# MK1.net
KiCad netlist of a schematic drawn in EAGLE
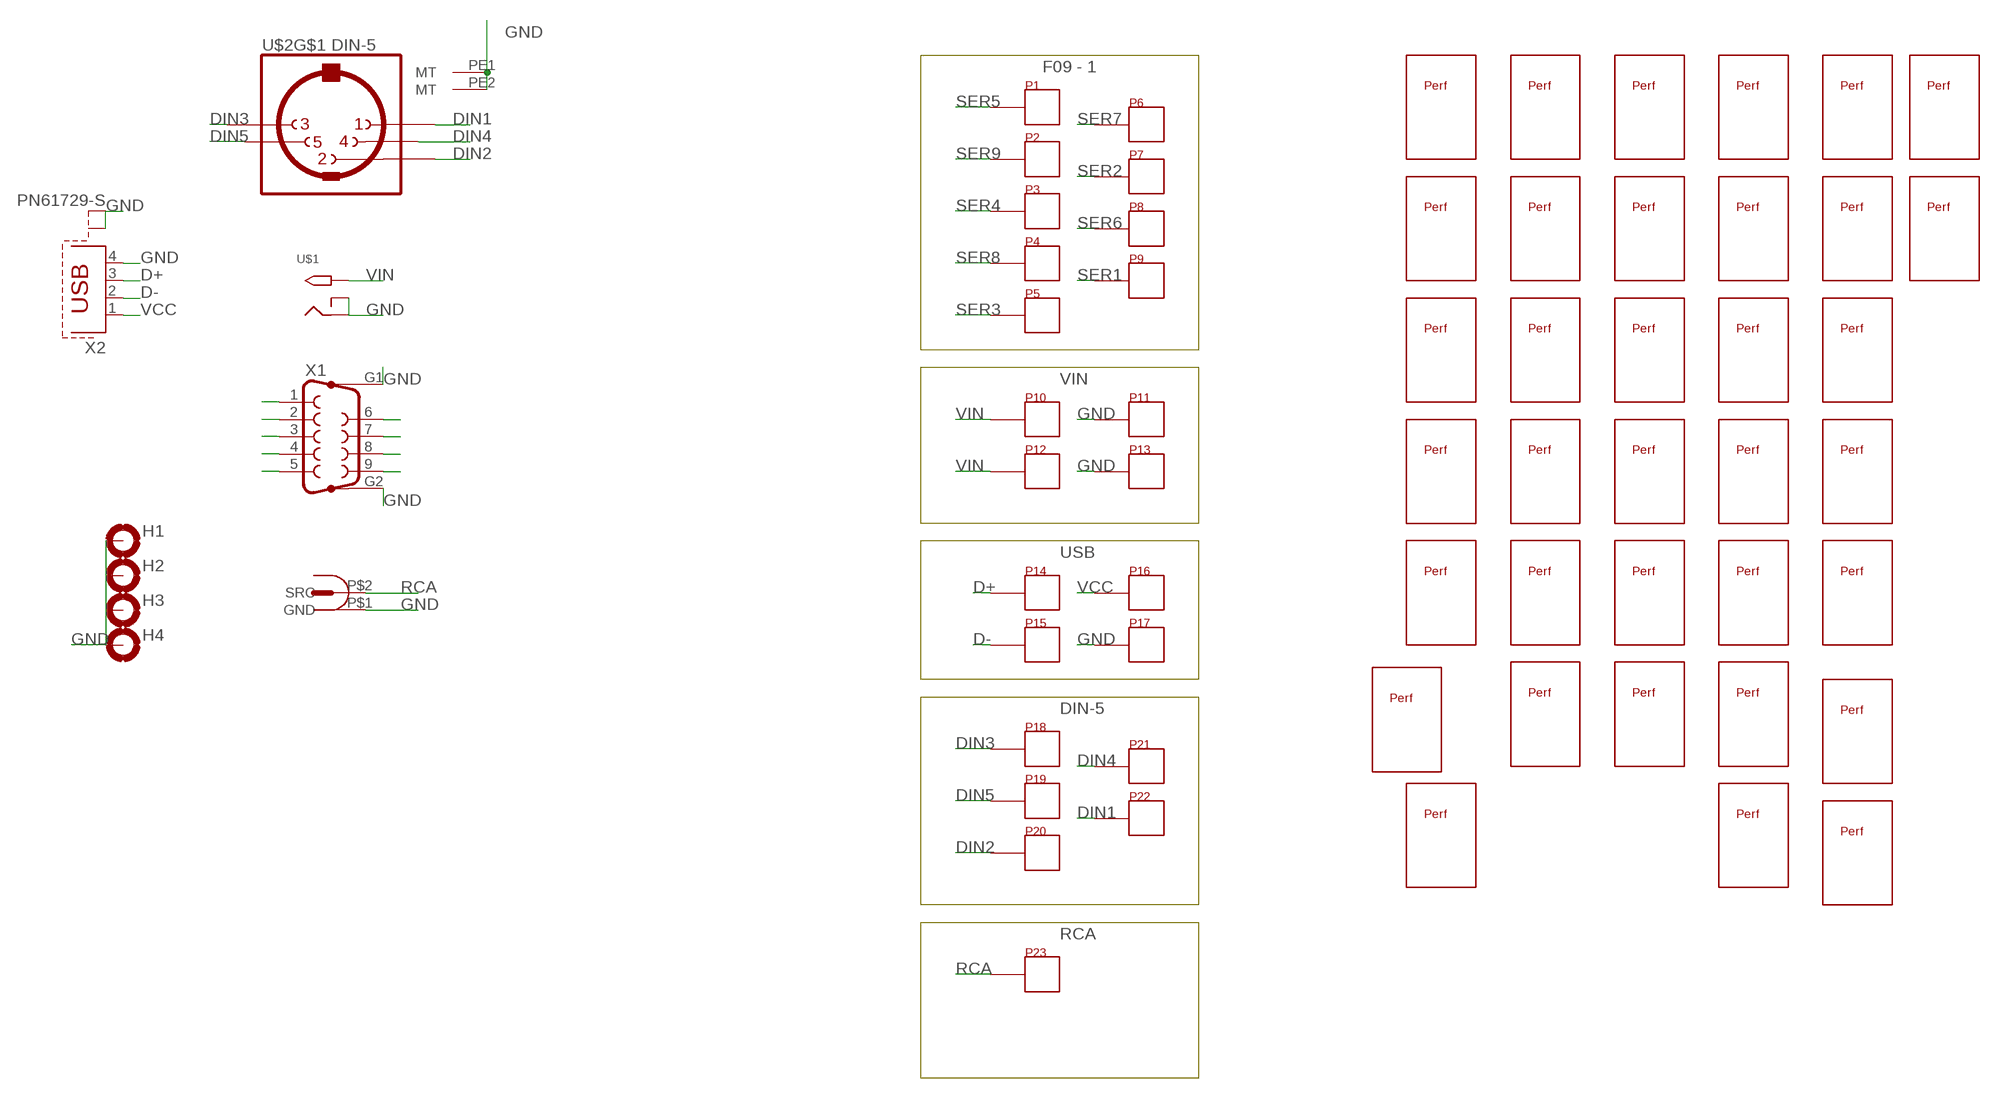
[diagram p0: schematic, sheet 1]

(export (version "E")
  (design (tool "Eeschema 10.0.6"))
  (components
    (comp (ref "H1")
      (value "MOUNT-PAD-ROUND3.0")
      (footprint "eagle-import:3,0-PAD")
      (libsource (lib "eagle-import") (part "MOUNT-PAD-ROUND3.0"))
    )
    (comp (ref "H2")
      (value "MOUNT-PAD-ROUND3.0")
      (footprint "eagle-import:3,0-PAD")
      (libsource (lib "eagle-import") (part "MOUNT-PAD-ROUND3.0"))
    )
    (comp (ref "H3")
      (value "MOUNT-PAD-ROUND3.0")
      (footprint "eagle-import:3,0-PAD")
      (libsource (lib "eagle-import") (part "MOUNT-PAD-ROUND3.0"))
    )
    (comp (ref "H4")
      (value "MOUNT-PAD-ROUND3.0")
      (footprint "eagle-import:3,0-PAD")
      (libsource (lib "eagle-import") (part "MOUNT-PAD-ROUND3.0"))
    )
    (comp (ref "P1")
      (value "X3-PAD")
      (footprint "eagle-import:X3-PAD")
      (libsource (lib "eagle-import") (part "X3-PAD"))
    )
    (comp (ref "P2")
      (value "X3-PAD")
      (footprint "eagle-import:X3-PAD")
      (libsource (lib "eagle-import") (part "X3-PAD"))
    )
    (comp (ref "P3")
      (value "X3-PAD")
      (footprint "eagle-import:X3-PAD")
      (libsource (lib "eagle-import") (part "X3-PAD"))
    )
    (comp (ref "P4")
      (value "X3-PAD")
      (footprint "eagle-import:X3-PAD")
      (libsource (lib "eagle-import") (part "X3-PAD"))
    )
    (comp (ref "P5")
      (value "X3-PAD")
      (footprint "eagle-import:X3-PAD")
      (libsource (lib "eagle-import") (part "X3-PAD"))
    )
    (comp (ref "P6")
      (value "X3-PAD")
      (footprint "eagle-import:X3-PAD")
      (libsource (lib "eagle-import") (part "X3-PAD"))
    )
    (comp (ref "P7")
      (value "X3-PAD")
      (footprint "eagle-import:X3-PAD")
      (libsource (lib "eagle-import") (part "X3-PAD"))
    )
    (comp (ref "P8")
      (value "X3-PAD")
      (footprint "eagle-import:X3-PAD")
      (libsource (lib "eagle-import") (part "X3-PAD"))
    )
    (comp (ref "P9")
      (value "X3-PAD")
      (footprint "eagle-import:X3-PAD")
      (libsource (lib "eagle-import") (part "X3-PAD"))
    )
    (comp (ref "P10")
      (value "X3-PAD")
      (footprint "eagle-import:X3-PAD")
      (libsource (lib "eagle-import") (part "X3-PAD"))
    )
    (comp (ref "P11")
      (value "X3-PAD")
      (footprint "eagle-import:X3-PAD")
      (libsource (lib "eagle-import") (part "X3-PAD"))
    )
    (comp (ref "P12")
      (value "X3-PAD")
      (footprint "eagle-import:X3-PAD")
      (libsource (lib "eagle-import") (part "X3-PAD"))
    )
    (comp (ref "P13")
      (value "X3-PAD")
      (footprint "eagle-import:X3-PAD")
      (libsource (lib "eagle-import") (part "X3-PAD"))
    )
    (comp (ref "P14")
      (value "X3-PAD")
      (footprint "eagle-import:X3-PAD")
      (libsource (lib "eagle-import") (part "X3-PAD"))
    )
    (comp (ref "P15")
      (value "X3-PAD")
      (footprint "eagle-import:X3-PAD")
      (libsource (lib "eagle-import") (part "X3-PAD"))
    )
    (comp (ref "P16")
      (value "X3-PAD")
      (footprint "eagle-import:X3-PAD")
      (libsource (lib "eagle-import") (part "X3-PAD"))
    )
    (comp (ref "P17")
      (value "X3-PAD")
      (footprint "eagle-import:X3-PAD")
      (libsource (lib "eagle-import") (part "X3-PAD"))
    )
    (comp (ref "P18")
      (value "X3-PAD")
      (footprint "eagle-import:X3-PAD")
      (libsource (lib "eagle-import") (part "X3-PAD"))
    )
    (comp (ref "P19")
      (value "X3-PAD")
      (footprint "eagle-import:X3-PAD")
      (libsource (lib "eagle-import") (part "X3-PAD"))
    )
    (comp (ref "P20")
      (value "X3-PAD")
      (footprint "eagle-import:X3-PAD")
      (libsource (lib "eagle-import") (part "X3-PAD"))
    )
    (comp (ref "P21")
      (value "X3-PAD")
      (footprint "eagle-import:X3-PAD")
      (libsource (lib "eagle-import") (part "X3-PAD"))
    )
    (comp (ref "P22")
      (value "X3-PAD")
      (footprint "eagle-import:X3-PAD")
      (libsource (lib "eagle-import") (part "X3-PAD"))
    )
    (comp (ref "P23")
      (value "X3-PAD")
      (footprint "eagle-import:X3-PAD")
      (libsource (lib "eagle-import") (part "X3-PAD"))
    )
    (comp (ref "U$1")
      (value "2.1MMJACKTHM")
      (footprint "eagle-import:PJ-102A")
      (libsource (lib "eagle-import") (part "2.1MMJACKTHM"))
    )
    (comp (ref "U$2")
      (value "DIN-5")
      (footprint "eagle-import:CP-2350")
      (libsource (lib "eagle-import") (part "MIDIJACK"))
    )
    (comp (ref "U$3")
      (value "PERF")
      (footprint "eagle-import:PERF")
      (libsource (lib "eagle-import") (part "PERF"))
    )
    (comp (ref "U$4")
      (value "PERF")
      (footprint "eagle-import:PERF")
      (libsource (lib "eagle-import") (part "PERF"))
    )
    (comp (ref "U$5")
      (value "PERF")
      (footprint "eagle-import:PERF")
      (libsource (lib "eagle-import") (part "PERF"))
    )
    (comp (ref "U$6")
      (value "PERF")
      (footprint "eagle-import:PERF")
      (libsource (lib "eagle-import") (part "PERF"))
    )
    (comp (ref "U$7")
      (value "PERF")
      (footprint "eagle-import:PERF")
      (libsource (lib "eagle-import") (part "PERF"))
    )
    (comp (ref "U$8")
      (value "PERF")
      (footprint "eagle-import:PERF")
      (libsource (lib "eagle-import") (part "PERF"))
    )
    (comp (ref "U$9")
      (value "PERF")
      (footprint "eagle-import:PERF")
      (libsource (lib "eagle-import") (part "PERF"))
    )
    (comp (ref "U$10")
      (value "PERF")
      (footprint "eagle-import:PERF")
      (libsource (lib "eagle-import") (part "PERF"))
    )
    (comp (ref "U$11")
      (value "PERF")
      (footprint "eagle-import:PERF")
      (libsource (lib "eagle-import") (part "PERF"))
    )
    (comp (ref "U$12")
      (value "PERF")
      (footprint "eagle-import:PERF")
      (libsource (lib "eagle-import") (part "PERF"))
    )
    (comp (ref "U$13")
      (value "PERF")
      (footprint "eagle-import:PERF")
      (libsource (lib "eagle-import") (part "PERF"))
    )
    (comp (ref "U$14")
      (value "PERF")
      (footprint "eagle-import:PERF")
      (libsource (lib "eagle-import") (part "PERF"))
    )
    (comp (ref "U$15")
      (value "PERF")
      (footprint "eagle-import:PERF")
      (libsource (lib "eagle-import") (part "PERF"))
    )
    (comp (ref "U$16")
      (value "PERF")
      (footprint "eagle-import:PERF")
      (libsource (lib "eagle-import") (part "PERF"))
    )
    (comp (ref "U$17")
      (value "PERF")
      (footprint "eagle-import:PERF")
      (libsource (lib "eagle-import") (part "PERF"))
    )
    (comp (ref "U$18")
      (value "PERF")
      (footprint "eagle-import:PERF")
      (libsource (lib "eagle-import") (part "PERF"))
    )
    (comp (ref "U$19")
      (value "PERF")
      (footprint "eagle-import:PERF")
      (libsource (lib "eagle-import") (part "PERF"))
    )
    (comp (ref "U$20")
      (value "PERF")
      (footprint "eagle-import:PERF")
      (libsource (lib "eagle-import") (part "PERF"))
    )
    (comp (ref "U$21")
      (value "PERF")
      (footprint "eagle-import:PERF")
      (libsource (lib "eagle-import") (part "PERF"))
    )
    (comp (ref "U$22")
      (value "PERF")
      (footprint "eagle-import:PERF")
      (libsource (lib "eagle-import") (part "PERF"))
    )
    (comp (ref "U$23")
      (value "PERF")
      (footprint "eagle-import:PERF")
      (libsource (lib "eagle-import") (part "PERF"))
    )
    (comp (ref "U$24")
      (value "PERF")
      (footprint "eagle-import:PERF")
      (libsource (lib "eagle-import") (part "PERF"))
    )
    (comp (ref "U$25")
      (value "PERF")
      (footprint "eagle-import:PERF")
      (libsource (lib "eagle-import") (part "PERF"))
    )
    (comp (ref "U$26")
      (value "PERF")
      (footprint "eagle-import:PERF")
      (libsource (lib "eagle-import") (part "PERF"))
    )
    (comp (ref "U$27")
      (value "PERF")
      (footprint "eagle-import:PERF")
      (libsource (lib "eagle-import") (part "PERF"))
    )
    (comp (ref "U$28")
      (value "PERF")
      (footprint "eagle-import:PERF")
      (libsource (lib "eagle-import") (part "PERF"))
    )
    (comp (ref "U$29")
      (value "PERF")
      (footprint "eagle-import:PERF")
      (libsource (lib "eagle-import") (part "PERF"))
    )
    (comp (ref "U$30")
      (value "PERF")
      (footprint "eagle-import:PERF")
      (libsource (lib "eagle-import") (part "PERF"))
    )
    (comp (ref "U$31")
      (value "PERF")
      (footprint "eagle-import:PERF")
      (libsource (lib "eagle-import") (part "PERF"))
    )
    (comp (ref "U$32")
      (value "PERF")
      (footprint "eagle-import:PERF")
      (libsource (lib "eagle-import") (part "PERF"))
    )
    (comp (ref "U$33")
      (value "PERF")
      (footprint "eagle-import:PERF")
      (libsource (lib "eagle-import") (part "PERF"))
    )
    (comp (ref "U$34")
      (value "PERF")
      (footprint "eagle-import:PERF")
      (libsource (lib "eagle-import") (part "PERF"))
    )
    (comp (ref "U$35")
      (value "PERF")
      (footprint "eagle-import:PERF")
      (libsource (lib "eagle-import") (part "PERF"))
    )
    (comp (ref "U$36")
      (value "PERF")
      (footprint "eagle-import:PERF")
      (libsource (lib "eagle-import") (part "PERF"))
    )
    (comp (ref "U$37")
      (value "PERF")
      (footprint "eagle-import:PERF")
      (libsource (lib "eagle-import") (part "PERF"))
    )
    (comp (ref "U$38")
      (value "RCA_VIDEO")
      (footprint "eagle-import:RCA_VIDEO")
      (libsource (lib "eagle-import") (part "RCA_VIDEO"))
    )
    (comp (ref "X1")
      (value "F09HP")
      (footprint "eagle-import:F09HP")
      (libsource (lib "eagle-import") (part "F09HP"))
    )
    (comp (ref "X2")
      (value "PN61729-S")
      (footprint "eagle-import:PN61729-S")
      (libsource (lib "eagle-import") (part "PN61729-S"))
    )
  )
  (nets
    (net (code "1") (name "/D+") (class "Default")
      (node (ref "P14") (pin "1") (pinfunction "1_1") (pintype "bidirectional"))
      (node (ref "P14") (pin "2") (pinfunction "1_2") (pintype "bidirectional"))
      (node (ref "P14") (pin "3") (pinfunction "1_3") (pintype "bidirectional"))
      (node (ref "X2") (pin "3") (pinfunction "3_3") (pintype "passive"))
    )
    (net (code "2") (name "/D-") (class "Default")
      (node (ref "P15") (pin "1") (pinfunction "1_1") (pintype "bidirectional"))
      (node (ref "P15") (pin "2") (pinfunction "1_2") (pintype "bidirectional"))
      (node (ref "P15") (pin "3") (pinfunction "1_3") (pintype "bidirectional"))
      (node (ref "X2") (pin "2") (pinfunction "2_2") (pintype "passive"))
    )
    (net (code "3") (name "/DIN1") (class "Default")
      (node (ref "P22") (pin "1") (pinfunction "1_1") (pintype "bidirectional"))
      (node (ref "P22") (pin "2") (pinfunction "1_2") (pintype "bidirectional"))
      (node (ref "P22") (pin "3") (pinfunction "1_3") (pintype "bidirectional"))
      (node (ref "U$2") (pin "1") (pinfunction "1_1") (pintype "passive"))
    )
    (net (code "4") (name "/DIN2") (class "Default")
      (node (ref "P20") (pin "1") (pinfunction "1_1") (pintype "bidirectional"))
      (node (ref "P20") (pin "2") (pinfunction "1_2") (pintype "bidirectional"))
      (node (ref "P20") (pin "3") (pinfunction "1_3") (pintype "bidirectional"))
      (node (ref "U$2") (pin "2") (pinfunction "2_2") (pintype "passive"))
    )
    (net (code "5") (name "/DIN3") (class "Default")
      (node (ref "P18") (pin "1") (pinfunction "1_1") (pintype "bidirectional"))
      (node (ref "P18") (pin "2") (pinfunction "1_2") (pintype "bidirectional"))
      (node (ref "P18") (pin "3") (pinfunction "1_3") (pintype "bidirectional"))
      (node (ref "U$2") (pin "3") (pinfunction "3_3") (pintype "passive"))
    )
    (net (code "6") (name "/DIN4") (class "Default")
      (node (ref "P21") (pin "1") (pinfunction "1_1") (pintype "bidirectional"))
      (node (ref "P21") (pin "2") (pinfunction "1_2") (pintype "bidirectional"))
      (node (ref "P21") (pin "3") (pinfunction "1_3") (pintype "bidirectional"))
      (node (ref "U$2") (pin "4") (pinfunction "4_4") (pintype "passive"))
    )
    (net (code "7") (name "/DIN5") (class "Default")
      (node (ref "P19") (pin "1") (pinfunction "1_1") (pintype "bidirectional"))
      (node (ref "P19") (pin "2") (pinfunction "1_2") (pintype "bidirectional"))
      (node (ref "P19") (pin "3") (pinfunction "1_3") (pintype "bidirectional"))
      (node (ref "U$2") (pin "5") (pinfunction "5_5") (pintype "passive"))
    )
    (net (code "8") (name "/GND") (class "Default")
      (node (ref "H1") (pin "B3,0") (pinfunction "MOUNT_B3,0") (pintype "passive"))
      (node (ref "H2") (pin "B3,0") (pinfunction "MOUNT_B3,0") (pintype "passive"))
      (node (ref "H3") (pin "B3,0") (pinfunction "MOUNT_B3,0") (pintype "passive"))
      (node (ref "H4") (pin "B3,0") (pinfunction "MOUNT_B3,0") (pintype "passive"))
      (node (ref "P11") (pin "1") (pinfunction "1_1") (pintype "bidirectional"))
      (node (ref "P11") (pin "2") (pinfunction "1_2") (pintype "bidirectional"))
      (node (ref "P11") (pin "3") (pinfunction "1_3") (pintype "bidirectional"))
      (node (ref "P13") (pin "1") (pinfunction "1_1") (pintype "bidirectional"))
      (node (ref "P13") (pin "2") (pinfunction "1_2") (pintype "bidirectional"))
      (node (ref "P13") (pin "3") (pinfunction "1_3") (pintype "bidirectional"))
      (node (ref "P17") (pin "1") (pinfunction "1_1") (pintype "bidirectional"))
      (node (ref "P17") (pin "2") (pinfunction "1_2") (pintype "bidirectional"))
      (node (ref "P17") (pin "3") (pinfunction "1_3") (pintype "bidirectional"))
      (node (ref "U$1") (pin "RING") (pinfunction "RING_RING") (pintype "bidirectional"))
      (node (ref "U$1") (pin "RING_SW") (pinfunction "RING_SW_RING_SW") (pintype "bidirectional"))
      (node (ref "U$2") (pin "PE1") (pinfunction "MT_PE1") (pintype "passive"))
      (node (ref "U$2") (pin "PE2") (pinfunction "MT_PE2") (pintype "passive"))
      (node (ref "U$38") (pin "P$1") (pinfunction "GND_P$1") (pintype "bidirectional"))
      (node (ref "X1") (pin "G1") (pinfunction "G1_G1") (pintype "passive"))
      (node (ref "X1") (pin "G2") (pinfunction "G2_G2") (pintype "passive"))
      (node (ref "X2") (pin "4") (pinfunction "4_4") (pintype "passive"))
      (node (ref "X2") (pin "S1") (pinfunction "S1_S1") (pintype "passive"))
      (node (ref "X2") (pin "S2") (pinfunction "S2_S2") (pintype "passive"))
    )
    (net (code "9") (name "/RCA") (class "Default")
      (node (ref "P23") (pin "1") (pinfunction "1_1") (pintype "bidirectional"))
      (node (ref "P23") (pin "2") (pinfunction "1_2") (pintype "bidirectional"))
      (node (ref "P23") (pin "3") (pinfunction "1_3") (pintype "bidirectional"))
      (node (ref "U$38") (pin "P$2") (pinfunction "SRC_P$2") (pintype "bidirectional"))
    )
    (net (code "10") (name "/SER1") (class "Default")
      (node (ref "P9") (pin "1") (pinfunction "1_1") (pintype "bidirectional"))
      (node (ref "P9") (pin "2") (pinfunction "1_2") (pintype "bidirectional"))
      (node (ref "P9") (pin "3") (pinfunction "1_3") (pintype "bidirectional"))
      (node (ref "X1") (pin "1") (pinfunction "1_1") (pintype "passive"))
    )
    (net (code "11") (name "/SER2") (class "Default")
      (node (ref "P7") (pin "1") (pinfunction "1_1") (pintype "bidirectional"))
      (node (ref "P7") (pin "2") (pinfunction "1_2") (pintype "bidirectional"))
      (node (ref "P7") (pin "3") (pinfunction "1_3") (pintype "bidirectional"))
      (node (ref "X1") (pin "2") (pinfunction "2_2") (pintype "passive"))
    )
    (net (code "12") (name "/SER3") (class "Default")
      (node (ref "P5") (pin "1") (pinfunction "1_1") (pintype "bidirectional"))
      (node (ref "P5") (pin "2") (pinfunction "1_2") (pintype "bidirectional"))
      (node (ref "P5") (pin "3") (pinfunction "1_3") (pintype "bidirectional"))
      (node (ref "X1") (pin "3") (pinfunction "3_3") (pintype "passive"))
    )
    (net (code "13") (name "/SER4") (class "Default")
      (node (ref "P3") (pin "1") (pinfunction "1_1") (pintype "bidirectional"))
      (node (ref "P3") (pin "2") (pinfunction "1_2") (pintype "bidirectional"))
      (node (ref "P3") (pin "3") (pinfunction "1_3") (pintype "bidirectional"))
      (node (ref "X1") (pin "4") (pinfunction "4_4") (pintype "passive"))
    )
    (net (code "14") (name "/SER5") (class "Default")
      (node (ref "P1") (pin "1") (pinfunction "1_1") (pintype "bidirectional"))
      (node (ref "P1") (pin "2") (pinfunction "1_2") (pintype "bidirectional"))
      (node (ref "P1") (pin "3") (pinfunction "1_3") (pintype "bidirectional"))
      (node (ref "X1") (pin "5") (pinfunction "5_5") (pintype "passive"))
    )
    (net (code "15") (name "/SER6") (class "Default")
      (node (ref "P8") (pin "1") (pinfunction "1_1") (pintype "bidirectional"))
      (node (ref "P8") (pin "2") (pinfunction "1_2") (pintype "bidirectional"))
      (node (ref "P8") (pin "3") (pinfunction "1_3") (pintype "bidirectional"))
      (node (ref "X1") (pin "6") (pinfunction "6_6") (pintype "passive"))
    )
    (net (code "16") (name "/SER7") (class "Default")
      (node (ref "P6") (pin "1") (pinfunction "1_1") (pintype "bidirectional"))
      (node (ref "P6") (pin "2") (pinfunction "1_2") (pintype "bidirectional"))
      (node (ref "P6") (pin "3") (pinfunction "1_3") (pintype "bidirectional"))
      (node (ref "X1") (pin "7") (pinfunction "7_7") (pintype "passive"))
    )
    (net (code "17") (name "/SER8") (class "Default")
      (node (ref "P4") (pin "1") (pinfunction "1_1") (pintype "bidirectional"))
      (node (ref "P4") (pin "2") (pinfunction "1_2") (pintype "bidirectional"))
      (node (ref "P4") (pin "3") (pinfunction "1_3") (pintype "bidirectional"))
      (node (ref "X1") (pin "8") (pinfunction "8_8") (pintype "passive"))
    )
    (net (code "18") (name "/SER9") (class "Default")
      (node (ref "P2") (pin "1") (pinfunction "1_1") (pintype "bidirectional"))
      (node (ref "P2") (pin "2") (pinfunction "1_2") (pintype "bidirectional"))
      (node (ref "P2") (pin "3") (pinfunction "1_3") (pintype "bidirectional"))
      (node (ref "X1") (pin "9") (pinfunction "9_9") (pintype "passive"))
    )
    (net (code "19") (name "/VCC") (class "Default")
      (node (ref "P16") (pin "1") (pinfunction "1_1") (pintype "bidirectional"))
      (node (ref "P16") (pin "2") (pinfunction "1_2") (pintype "bidirectional"))
      (node (ref "P16") (pin "3") (pinfunction "1_3") (pintype "bidirectional"))
      (node (ref "X2") (pin "1") (pinfunction "1_1") (pintype "passive"))
    )
    (net (code "20") (name "/VIN") (class "Default")
      (node (ref "P10") (pin "1") (pinfunction "1_1") (pintype "bidirectional"))
      (node (ref "P10") (pin "2") (pinfunction "1_2") (pintype "bidirectional"))
      (node (ref "P10") (pin "3") (pinfunction "1_3") (pintype "bidirectional"))
      (node (ref "P12") (pin "1") (pinfunction "1_1") (pintype "bidirectional"))
      (node (ref "P12") (pin "2") (pinfunction "1_2") (pintype "bidirectional"))
      (node (ref "P12") (pin "3") (pinfunction "1_3") (pintype "bidirectional"))
      (node (ref "U$1") (pin "TIP") (pinfunction "TIP_TIP") (pintype "bidirectional"))
    )
  )
)
